# Steering_Wheel_rev0.net
KiCad netlist of a schematic drawn in EAGLE
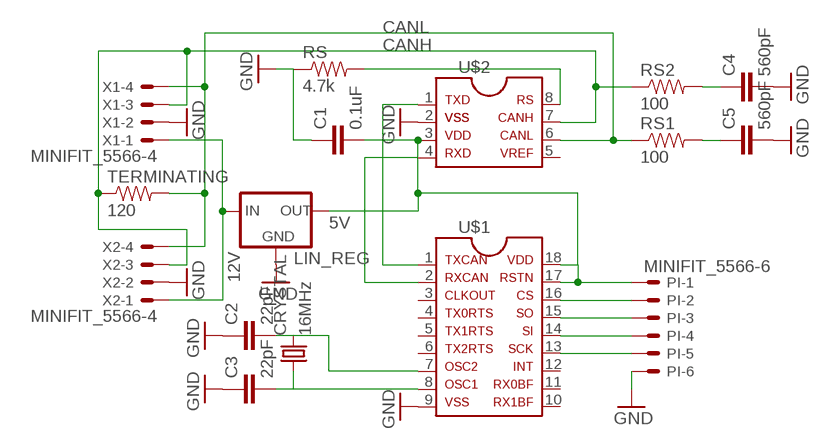
[diagram p0: schematic, sheet 1]

(export (version "E")
  (design (tool "Eeschema 10.0.6"))
  (components
    (comp (ref "C1")
      (value "0.1uF")
      (footprint "eagle-import:0805")
      (libsource (lib "eagle-import") (part "CAP0805"))
    )
    (comp (ref "C2")
      (value "22pF")
      (footprint "eagle-import:0805")
      (libsource (lib "eagle-import") (part "CAP0805"))
    )
    (comp (ref "C3")
      (value "22pF")
      (footprint "eagle-import:0805")
      (libsource (lib "eagle-import") (part "CAP0805"))
    )
    (comp (ref "C4")
      (value "560pF")
      (footprint "eagle-import:0805")
      (libsource (lib "eagle-import") (part "CAP0805"))
    )
    (comp (ref "C5")
      (value "560pF")
      (footprint "eagle-import:0805")
      (libsource (lib "eagle-import") (part "CAP0805"))
    )
    (comp (ref "CRYSTAL")
      (value "16MHz")
      (footprint "eagle-import:HC49UP")
      (libsource (lib "eagle-import") (part "CRYSTALSMD"))
    )
    (comp (ref "LIN_REG")
      (value "5V_REGULATOR_LM340-NLM340MPX-5.0/NOPB")
      (footprint "eagle-import:SOT223")
      (libsource (lib "eagle-import") (part "5V_REGULATOR_LM340-NLM340MPX-5.0/NOPB"))
    )
    (comp (ref "PI")
      (value "MINIFIT_5566-6")
      (footprint "eagle-import:MINIFIT_5566-6")
      (fields (field (name "MPN") "95566-61002"))
      (libsource (lib "eagle-import") (part "MINIFIT_5566-6"))
    )
    (comp (ref "RS")
      (value "4.7k")
      (footprint "eagle-import:0805")
      (libsource (lib "eagle-import") (part "RESISTOR0805-RES"))
    )
    (comp (ref "RS1")
      (value "100")
      (footprint "eagle-import:0805")
      (libsource (lib "eagle-import") (part "RESISTOR0805-RES"))
    )
    (comp (ref "RS2")
      (value "100")
      (footprint "eagle-import:0805")
      (libsource (lib "eagle-import") (part "RESISTOR0805-RES"))
    )
    (comp (ref "TERMINATING")
      (value "120")
      (footprint "eagle-import:0805")
      (libsource (lib "eagle-import") (part "RESISTOR0805-RES"))
    )
    (comp (ref "U$1")
      (value "MCP2515SMD")
      (footprint "eagle-import:SOIC-18W")
      (libsource (lib "eagle-import") (part "MCP2515SMD"))
    )
    (comp (ref "U$2")
      (value "MCP2551")
      (footprint "eagle-import:SOIC-08")
      (libsource (lib "eagle-import") (part "MCP2551"))
    )
    (comp (ref "X1")
      (value "MINIFIT_5566-4")
      (footprint "eagle-import:MINIFIT_5566-4")
      (libsource (lib "eagle-import") (part "MINIFIT_5566-4"))
    )
    (comp (ref "X2")
      (value "MINIFIT_5566-4")
      (footprint "eagle-import:MINIFIT_5566-4")
      (libsource (lib "eagle-import") (part "MINIFIT_5566-4"))
    )
  )
  (nets
    (net (code "1") (name "/5V") (class "Default")
      (node (ref "C1") (pin "2") (pinfunction "2_2") (pintype "passive"))
      (node (ref "LIN_REG") (pin "3") (pinfunction "OUT_3") (pintype "output"))
      (node (ref "PI") (pin "1") (pinfunction "S_1") (pintype "passive"))
      (node (ref "U$1") (pin "17") (pinfunction "17_17") (pintype "passive"))
      (node (ref "U$1") (pin "18") (pinfunction "18_18") (pintype "passive"))
      (node (ref "U$2") (pin "3") (pinfunction "3_3") (pintype "passive"))
    )
    (net (code "2") (name "/12V") (class "Default")
      (node (ref "LIN_REG") (pin "1") (pinfunction "IN_1") (pintype "input"))
      (node (ref "X1") (pin "1") (pinfunction "S_1") (pintype "passive"))
      (node (ref "X2") (pin "1") (pinfunction "S_1") (pintype "passive"))
    )
    (net (code "3") (name "/CANH") (class "Default")
      (node (ref "RS2") (pin "1") (pinfunction "1_1") (pintype "passive"))
      (node (ref "TERMINATING") (pin "1") (pinfunction "1_1") (pintype "passive"))
      (node (ref "U$2") (pin "7") (pinfunction "7_7") (pintype "passive"))
      (node (ref "X1") (pin "3") (pinfunction "S_3") (pintype "passive"))
      (node (ref "X2") (pin "3") (pinfunction "S_3") (pintype "passive"))
    )
    (net (code "4") (name "/CANL") (class "Default")
      (node (ref "RS1") (pin "1") (pinfunction "1_1") (pintype "passive"))
      (node (ref "TERMINATING") (pin "2") (pinfunction "2_2") (pintype "passive"))
      (node (ref "U$2") (pin "6") (pinfunction "6_6") (pintype "passive"))
      (node (ref "X1") (pin "4") (pinfunction "S_4") (pintype "passive"))
      (node (ref "X2") (pin "4") (pinfunction "S_4") (pintype "passive"))
    )
    (net (code "5") (name "GND") (class "Default")
      (node (ref "C1") (pin "1") (pinfunction "1_1") (pintype "passive"))
      (node (ref "C2") (pin "1") (pinfunction "1_1") (pintype "passive"))
      (node (ref "C3") (pin "1") (pinfunction "1_1") (pintype "passive"))
      (node (ref "C4") (pin "2") (pinfunction "2_2") (pintype "passive"))
      (node (ref "C5") (pin "2") (pinfunction "2_2") (pintype "passive"))
      (node (ref "LIN_REG") (pin "2") (pinfunction "GND_2") (pintype "input"))
      (node (ref "LIN_REG") (pin "4") (pinfunction "GND_4") (pintype "input"))
      (node (ref "PI") (pin "6") (pinfunction "S_6") (pintype "passive"))
      (node (ref "RS") (pin "1") (pinfunction "1_1") (pintype "passive"))
      (node (ref "U$1") (pin "9") (pinfunction "9_9") (pintype "passive"))
      (node (ref "U$2") (pin "2") (pinfunction "2_2") (pintype "passive"))
      (node (ref "X1") (pin "2") (pinfunction "S_2") (pintype "passive"))
      (node (ref "X2") (pin "2") (pinfunction "S_2") (pintype "passive"))
    )
    (net (code "6") (name "Net-(C2-Pad2)") (class "Default")
      (node (ref "C2") (pin "2") (pinfunction "2_2") (pintype "passive"))
      (node (ref "CRYSTAL") (pin "2") (pinfunction "2_2") (pintype "passive"))
      (node (ref "U$1") (pin "7") (pinfunction "7_7") (pintype "passive"))
    )
    (net (code "7") (name "Net-(C3-Pad2)") (class "Default")
      (node (ref "C3") (pin "2") (pinfunction "2_2") (pintype "passive"))
      (node (ref "CRYSTAL") (pin "1") (pinfunction "1_1") (pintype "passive"))
      (node (ref "U$1") (pin "8") (pinfunction "8_8") (pintype "passive"))
    )
    (net (code "8") (name "Net-(C4-Pad1)") (class "Default")
      (node (ref "C4") (pin "1") (pinfunction "1_1") (pintype "passive"))
      (node (ref "RS2") (pin "2") (pinfunction "2_2") (pintype "passive"))
    )
    (net (code "9") (name "Net-(C5-Pad1)") (class "Default")
      (node (ref "C5") (pin "1") (pinfunction "1_1") (pintype "passive"))
      (node (ref "RS1") (pin "2") (pinfunction "2_2") (pintype "passive"))
    )
    (net (code "10") (name "Net-(PIB-S)") (class "Default")
      (node (ref "PI") (pin "2") (pinfunction "S_2") (pintype "passive"))
      (node (ref "U$1") (pin "16") (pinfunction "16_16") (pintype "passive"))
    )
    (net (code "11") (name "Net-(PIC-S)") (class "Default")
      (node (ref "PI") (pin "3") (pinfunction "S_3") (pintype "passive"))
      (node (ref "U$1") (pin "15") (pinfunction "15_15") (pintype "passive"))
    )
    (net (code "12") (name "Net-(PID-S)") (class "Default")
      (node (ref "PI") (pin "4") (pinfunction "S_4") (pintype "passive"))
      (node (ref "U$1") (pin "14") (pinfunction "14_14") (pintype "passive"))
    )
    (net (code "13") (name "Net-(PIE-S)") (class "Default")
      (node (ref "PI") (pin "5") (pinfunction "S_5") (pintype "passive"))
      (node (ref "U$1") (pin "13") (pinfunction "13_13") (pintype "passive"))
    )
    (net (code "14") (name "Net-(RS-Pad2)") (class "Default")
      (node (ref "RS") (pin "2") (pinfunction "2_2") (pintype "passive"))
      (node (ref "U$2") (pin "8") (pinfunction "8_8") (pintype "passive"))
    )
    (net (code "15") (name "Net-(U$1-Pad1)") (class "Default")
      (node (ref "U$1") (pin "1") (pinfunction "1_1") (pintype "passive"))
      (node (ref "U$2") (pin "1") (pinfunction "1_1") (pintype "passive"))
    )
    (net (code "16") (name "Net-(U$1-Pad2)") (class "Default")
      (node (ref "U$1") (pin "2") (pinfunction "2_2") (pintype "passive"))
      (node (ref "U$2") (pin "4") (pinfunction "4_4") (pintype "passive"))
    )
    (net (code "17") (name "unconnected-(U$1-Pad3)") (class "Default")
      (node (ref "U$1") (pin "3") (pinfunction "3_3") (pintype "passive"))
    )
    (net (code "18") (name "unconnected-(U$1-Pad4)") (class "Default")
      (node (ref "U$1") (pin "4") (pinfunction "4_4") (pintype "passive"))
    )
    (net (code "19") (name "unconnected-(U$1-Pad5)") (class "Default")
      (node (ref "U$1") (pin "5") (pinfunction "5_5") (pintype "passive"))
    )
    (net (code "20") (name "unconnected-(U$1-Pad6)") (class "Default")
      (node (ref "U$1") (pin "6") (pinfunction "6_6") (pintype "passive"))
    )
    (net (code "21") (name "unconnected-(U$1-Pad10)") (class "Default")
      (node (ref "U$1") (pin "10") (pinfunction "10_10") (pintype "passive"))
    )
    (net (code "22") (name "unconnected-(U$1-Pad11)") (class "Default")
      (node (ref "U$1") (pin "11") (pinfunction "11_11") (pintype "passive"))
    )
    (net (code "23") (name "unconnected-(U$1-Pad12)") (class "Default")
      (node (ref "U$1") (pin "12") (pinfunction "12_12") (pintype "passive"))
    )
    (net (code "24") (name "unconnected-(U$2-Pad5)") (class "Default")
      (node (ref "U$2") (pin "5") (pinfunction "5_5") (pintype "passive"))
    )
  )
)
